# Processor_Interface.net
KiCad netlist of a schematic drawn in Altium Designer
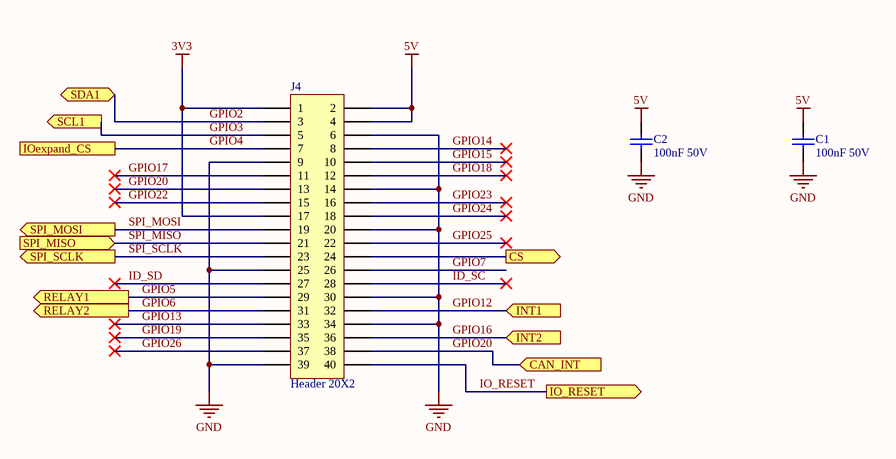
[diagram p0: Processor_Interface.SchDoc]

(export (version "E")
  (design (tool "Eeschema 10.0.6"))
  (components
    (comp (ref "C1")
      (value "100nF 50V")
      (footprint "0603C_L")
      (fields
        (field (name "MANUFACTURER") "Yageo")
        (field (name "MANUFACTURER PART NUMBER") "CC0603ZRY5V9BB104")
        (field (name "TOLERANCE") "-20%, +80%")
      )
      (libsource (lib "WCT") (part "Cap100nF_50V_0603"))
    )
    (comp (ref "C2")
      (value "100nF 50V")
      (footprint "0603C_L")
      (fields
        (field (name "MANUFACTURER") "Yageo")
        (field (name "MANUFACTURER PART NUMBER") "CC0603ZRY5V9BB104")
        (field (name "TOLERANCE") "-20%, +80%")
      )
      (libsource (lib "WCT") (part "Cap100nF_50V_0603"))
    )
    (comp (ref "J4")
      (value "Header 20X2")
      (footprint "HDR2X20")
      (description "Header, 20-Pin, Dual row")
      (fields (field (name "PUBLISHER") "Altium Limited"))
      (libsource (lib "Miscellaneous Connectors") (part "Header 20X2"))
    )
  )
  (nets
    (net (code "1") (name "/CS") (class "Default")
      (node (ref "J4") (pin "24") (pinfunction "24_24") (pintype "passive"))
    )
    (net (code "2") (name "/GPIO2") (class "Default")
      (node (ref "J4") (pin "3") (pinfunction "3_3") (pintype "passive"))
    )
    (net (code "3") (name "/GPIO3") (class "Default")
      (node (ref "J4") (pin "5") (pinfunction "5_5") (pintype "passive"))
    )
    (net (code "4") (name "/GPIO4") (class "Default")
      (node (ref "J4") (pin "7") (pinfunction "7_7") (pintype "passive"))
    )
    (net (code "5") (name "/GPIO5") (class "Default")
      (node (ref "J4") (pin "29") (pinfunction "29_29") (pintype "passive"))
    )
    (net (code "6") (name "/GPIO6") (class "Default")
      (node (ref "J4") (pin "31") (pinfunction "31_31") (pintype "passive"))
    )
    (net (code "7") (name "/GPIO7") (class "Default")
      (node (ref "J4") (pin "26") (pinfunction "26_26") (pintype "passive"))
    )
    (net (code "8") (name "/GPIO12") (class "Default")
      (node (ref "J4") (pin "32") (pinfunction "32_32") (pintype "passive"))
    )
    (net (code "9") (name "/GPIO13") (class "Default")
      (node (ref "J4") (pin "33") (pinfunction "33_33") (pintype "passive+no_connect"))
    )
    (net (code "10") (name "/GPIO14") (class "Default")
      (node (ref "J4") (pin "8") (pinfunction "8_8") (pintype "passive+no_connect"))
    )
    (net (code "11") (name "/GPIO15") (class "Default")
      (node (ref "J4") (pin "10") (pinfunction "10_10") (pintype "passive+no_connect"))
    )
    (net (code "12") (name "/GPIO16") (class "Default")
      (node (ref "J4") (pin "36") (pinfunction "36_36") (pintype "passive"))
    )
    (net (code "13") (name "/GPIO17") (class "Default")
      (node (ref "J4") (pin "11") (pinfunction "11_11") (pintype "passive+no_connect"))
    )
    (net (code "14") (name "/GPIO18") (class "Default")
      (node (ref "J4") (pin "12") (pinfunction "12_12") (pintype "passive+no_connect"))
    )
    (net (code "15") (name "/GPIO19") (class "Default")
      (node (ref "J4") (pin "35") (pinfunction "35_35") (pintype "passive+no_connect"))
    )
    (net (code "16") (name "/GPIO20") (class "Default")
      (node (ref "J4") (pin "13") (pinfunction "13_13") (pintype "passive"))
      (node (ref "J4") (pin "38") (pinfunction "38_38") (pintype "passive"))
    )
    (net (code "17") (name "/GPIO22") (class "Default")
      (node (ref "J4") (pin "15") (pinfunction "15_15") (pintype "passive+no_connect"))
    )
    (net (code "18") (name "/GPIO23") (class "Default")
      (node (ref "J4") (pin "16") (pinfunction "16_16") (pintype "passive+no_connect"))
    )
    (net (code "19") (name "/GPIO24") (class "Default")
      (node (ref "J4") (pin "18") (pinfunction "18_18") (pintype "passive+no_connect"))
    )
    (net (code "20") (name "/GPIO25") (class "Default")
      (node (ref "J4") (pin "22") (pinfunction "22_22") (pintype "passive+no_connect"))
    )
    (net (code "21") (name "/GPIO26") (class "Default")
      (node (ref "J4") (pin "37") (pinfunction "37_37") (pintype "passive+no_connect"))
    )
    (net (code "22") (name "/ID_SC") (class "Default")
      (node (ref "J4") (pin "28") (pinfunction "28_28") (pintype "passive+no_connect"))
    )
    (net (code "23") (name "/ID_SD") (class "Default")
      (node (ref "J4") (pin "27") (pinfunction "27_27") (pintype "passive+no_connect"))
    )
    (net (code "24") (name "/IO_RESET") (class "Default")
      (node (ref "J4") (pin "40") (pinfunction "40_40") (pintype "passive"))
    )
    (net (code "25") (name "/SPI_MISO") (class "Default")
      (node (ref "J4") (pin "21") (pinfunction "21_21") (pintype "passive"))
    )
    (net (code "26") (name "/SPI_MOSI") (class "Default")
      (node (ref "J4") (pin "19") (pinfunction "19_19") (pintype "passive"))
    )
    (net (code "27") (name "/SPI_SCLK") (class "Default")
      (node (ref "J4") (pin "23") (pinfunction "23_23") (pintype "passive"))
    )
    (net (code "28") (name "3V3") (class "Default")
      (node (ref "J4") (pin "1") (pinfunction "1_1") (pintype "passive"))
      (node (ref "J4") (pin "17") (pinfunction "17_17") (pintype "passive"))
    )
    (net (code "29") (name "5V") (class "Default")
      (node (ref "C1") (pin "2") (pinfunction "2_2") (pintype "passive"))
      (node (ref "C2") (pin "2") (pinfunction "2_2") (pintype "passive"))
      (node (ref "J4") (pin "2") (pinfunction "2_2") (pintype "passive"))
      (node (ref "J4") (pin "4") (pinfunction "4_4") (pintype "passive"))
    )
    (net (code "30") (name "GND") (class "Default")
      (node (ref "C1") (pin "1") (pinfunction "1_1") (pintype "passive"))
      (node (ref "C2") (pin "1") (pinfunction "1_1") (pintype "passive"))
      (node (ref "J4") (pin "14") (pinfunction "14_14") (pintype "passive"))
      (node (ref "J4") (pin "20") (pinfunction "20_20") (pintype "passive"))
      (node (ref "J4") (pin "25") (pinfunction "25_25") (pintype "passive"))
      (node (ref "J4") (pin "30") (pinfunction "30_30") (pintype "passive"))
      (node (ref "J4") (pin "34") (pinfunction "34_34") (pintype "passive"))
      (node (ref "J4") (pin "39") (pinfunction "39_39") (pintype "passive"))
      (node (ref "J4") (pin "6") (pinfunction "6_6") (pintype "passive"))
      (node (ref "J4") (pin "9") (pinfunction "9_9") (pintype "passive"))
    )
  )
)
